# Ethernet_PHY.net
KiCad netlist of a schematic drawn in Altium Designer
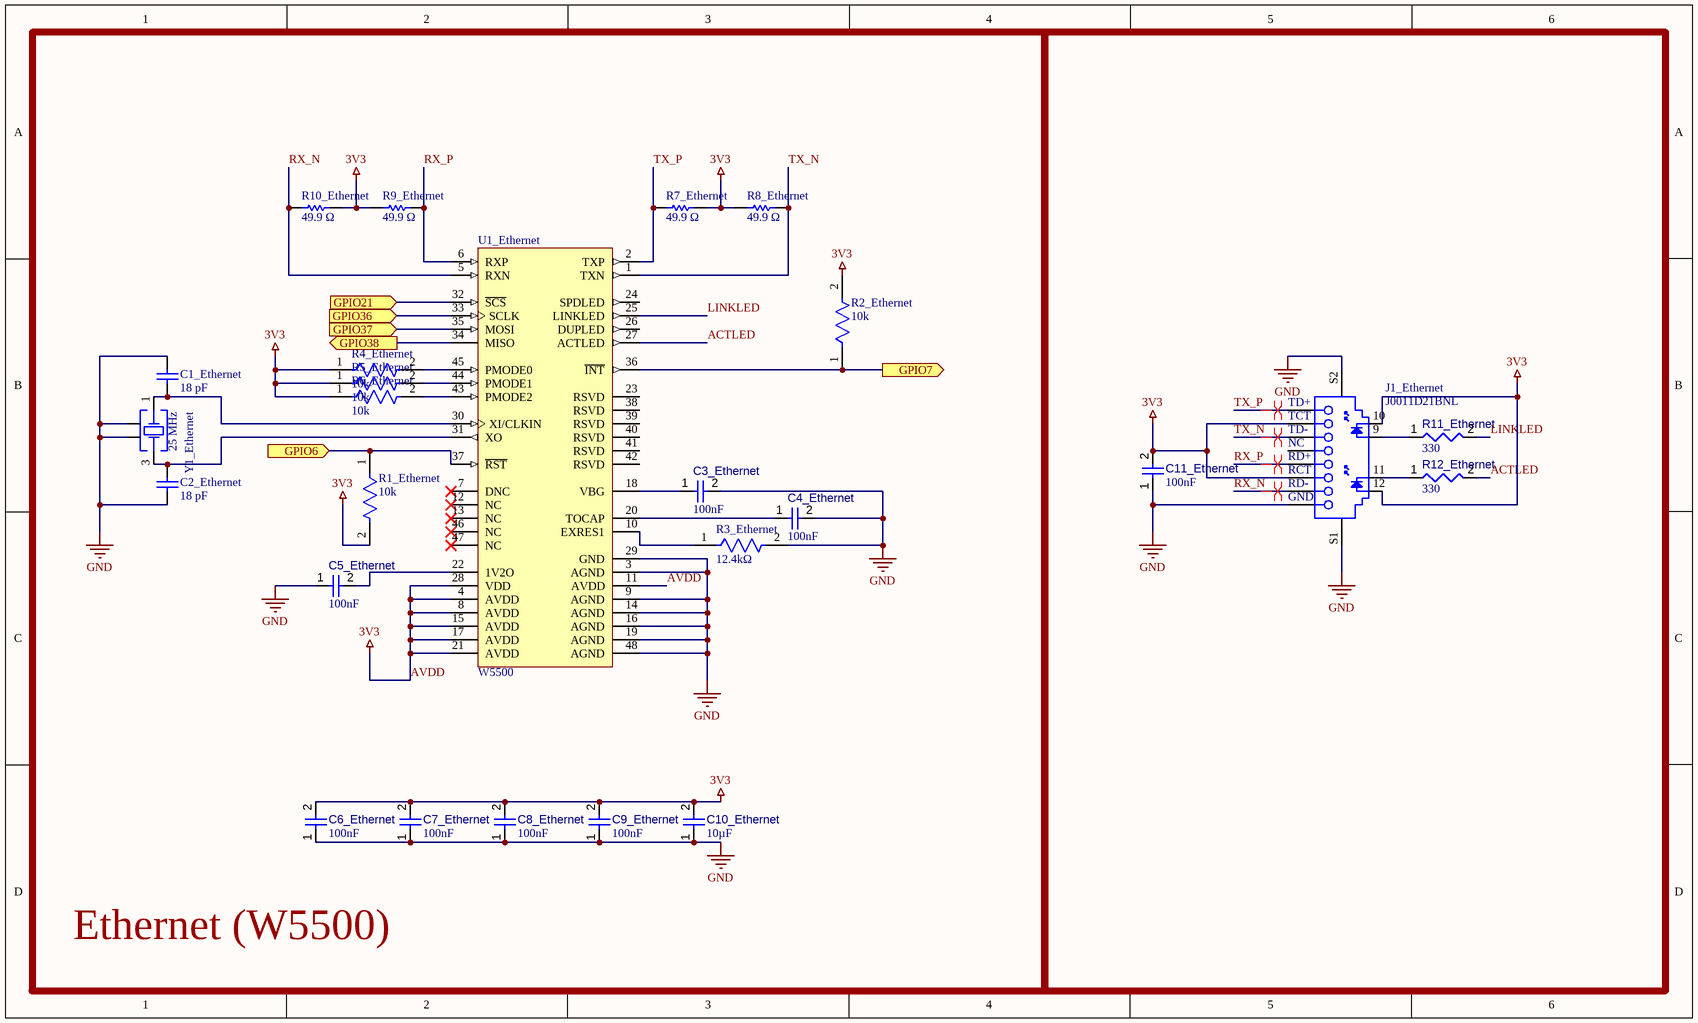
[diagram p0: Ethernet PHY.SchDoc]

(export (version "E")
  (design (tool "Eeschema 10.0.6"))
  (components
    (comp (ref "C1_Ethernet")
      (value "18 pF")
      (footprint "CAPC1608X90X35LL10T15")
      (description "Chip Capacitor, 18 pF, +/- 5%, 50 V, -55 to 125 degC, 0603 (1608 Metric), RoHS, Tape and Reel")
      (fields (field (name "TOLERANCE") "±5%") (field (name "MANUFACTURER") "Murata"))
      (libsource (lib "Altium Content Vault") (part "CAP-NP-2"))
    )
    (comp (ref "C2_Ethernet")
      (value "18 pF")
      (footprint "CAPC1608X90X35LL10T15")
      (description "Chip Capacitor, 18 pF, +/- 5%, 50 V, -55 to 125 degC, 0603 (1608 Metric), RoHS, Tape and Reel")
      (fields (field (name "TOLERANCE") "±5%") (field (name "MANUFACTURER") "Murata"))
      (libsource (lib "Altium Content Vault") (part "CAP-NP-2"))
    )
    (comp (ref "C3_Ethernet")
      (value "100nF")
      (footprint "CAPC0402(1005)60_L")
      (description "Chip Capacitor, 100nF +/-20%, 10V, 0402, Thickness 0.6 mm")
      (fields (field (name "TOLERANCE") "20%") (field (name "Comment") "Capacitor 100nF +/-20% 10V 0402"))
      (libsource (lib "Faiz Agunda") (part "CAP-NP-2"))
    )
    (comp (ref "C4_Ethernet")
      (value "100nF")
      (footprint "CAPC0402(1005)60_L")
      (description "Chip Capacitor, 100nF +/-20%, 10V, 0402, Thickness 0.6 mm")
      (fields (field (name "TOLERANCE") "20%") (field (name "Comment") "Capacitor 100nF +/-20% 10V 0402"))
      (libsource (lib "Faiz Agunda") (part "CAP-NP-2"))
    )
    (comp (ref "C5_Ethernet")
      (value "100nF")
      (footprint "CAPC0402(1005)60_L")
      (description "Chip Capacitor, 100nF +/-20%, 10V, 0402, Thickness 0.6 mm")
      (fields (field (name "TOLERANCE") "20%") (field (name "Comment") "Capacitor 100nF +/-20% 10V 0402"))
      (libsource (lib "Faiz Agunda") (part "CAP-NP-2"))
    )
    (comp (ref "C6_Ethernet")
      (value "100nF")
      (footprint "CAPC0402(1005)60_L")
      (description "Chip Capacitor, 100nF +/-20%, 10V, 0402, Thickness 0.6 mm")
      (fields (field (name "TOLERANCE") "20%") (field (name "Comment") "Capacitor 100nF +/-20% 10V 0402"))
      (libsource (lib "Faiz Agunda") (part "CAP-NP-2"))
    )
    (comp (ref "C7_Ethernet")
      (value "100nF")
      (footprint "CAPC0402(1005)60_L")
      (description "Chip Capacitor, 100nF +/-20%, 10V, 0402, Thickness 0.6 mm")
      (fields (field (name "TOLERANCE") "20%") (field (name "Comment") "Capacitor 100nF +/-20% 10V 0402"))
      (libsource (lib "Faiz Agunda") (part "CAP-NP-2"))
    )
    (comp (ref "C8_Ethernet")
      (value "100nF")
      (footprint "CAPC0402(1005)60_L")
      (description "Chip Capacitor, 100nF +/-20%, 10V, 0402, Thickness 0.6 mm")
      (fields (field (name "TOLERANCE") "20%") (field (name "Comment") "Capacitor 100nF +/-20% 10V 0402"))
      (libsource (lib "Faiz Agunda") (part "CAP-NP-2"))
    )
    (comp (ref "C9_Ethernet")
      (value "100nF")
      (footprint "CAPC0402(1005)60_L")
      (description "Chip Capacitor, 100nF +/-20%, 10V, 0402, Thickness 0.6 mm")
      (fields (field (name "TOLERANCE") "20%") (field (name "Comment") "Capacitor 100nF +/-20% 10V 0402"))
      (libsource (lib "Faiz Agunda") (part "CAP-NP-2"))
    )
    (comp (ref "C10_Ethernet")
      (value "10µF")
      (footprint "CAPC0603(1608)100_L")
      (description "Chip Capacitor, 10µF +/-20%, 10V, 0603, Thickness 1 mm")
      (fields (field (name "TOLERANCE") "10%") (field (name "Comment") "Capacitor 10µF +/-20% 10V 0603"))
      (libsource (lib "Faiz Agunda") (part "CAP-NP-2"))
    )
    (comp (ref "C11_Ethernet")
      (value "100nF")
      (footprint "CAPC0402(1005)60_L")
      (description "Chip Capacitor, 100nF +/-20%, 10V, 0402, Thickness 0.6 mm")
      (fields (field (name "TOLERANCE") "20%") (field (name "Comment") "Capacitor 100nF +/-20% 10V 0402"))
      (libsource (lib "Faiz Agunda") (part "CAP-NP-2"))
    )
    (comp (ref "J1_Ethernet")
      (value "J0011D21BNL")
      (footprint "PULS-J00XXD21XNL-B-12")
      (fields (field (name "MANUFACTURER") "Pulse"))
      (libsource (lib "Altium Content Vault") (part "PULS-RJ45-12-2SHLD"))
    )
    (comp (ref "R1_Ethernet")
      (value "10k")
      (footprint "FP-CRGCQ1206-IPC_C")
      (description "Res Thick Film 1206 10K Ohm 1% 0.25W(1/4W) ±100ppm/C Pad SMD Automotive T/R")
      (fields (field (name "TOLERANCE") "1%") (field (name "Comment") "CRGCQ1206F10K"))
      (libsource (lib "Faiz Agunda") (part "1029c3af85768c4190bb7ad29bc67b5"))
    )
    (comp (ref "R2_Ethernet")
      (value "10k")
      (footprint "FP-CRGCQ1206-IPC_C")
      (description "Res Thick Film 1206 10K Ohm 1% 0.25W(1/4W) ±100ppm/C Pad SMD Automotive T/R")
      (fields (field (name "TOLERANCE") "1%") (field (name "Comment") "CRGCQ1206F10K"))
      (libsource (lib "Faiz Agunda") (part "1029c3af85768c4190bb7ad29bc67b5"))
    )
    (comp (ref "R3_Ethernet")
      (value "12.4kΩ")
      (footprint "FP-TFCR0805-IPC_C")
      (description "RES Thin Film,  12.4kΩ, 0.1%, 0.1W, 25ppm/°C, 0805")
      (libsource (lib "Altium Content Vault") (part "1029c3af85768c4190bb7ad29bc67b5"))
    )
    (comp (ref "R4_Ethernet")
      (value "10k")
      (footprint "FP-CRGCQ1206-IPC_C")
      (description "Res Thick Film 1206 10K Ohm 1% 0.25W(1/4W) ±100ppm/C Pad SMD Automotive T/R")
      (fields (field (name "TOLERANCE") "1%") (field (name "Comment") "CRGCQ1206F10K"))
      (libsource (lib "Faiz Agunda") (part "1029c3af85768c4190bb7ad29bc67b5"))
    )
    (comp (ref "R5_Ethernet")
      (value "10k")
      (footprint "FP-CRGCQ1206-IPC_C")
      (description "Res Thick Film 1206 10K Ohm 1% 0.25W(1/4W) ±100ppm/C Pad SMD Automotive T/R")
      (fields (field (name "TOLERANCE") "1%") (field (name "Comment") "CRGCQ1206F10K"))
      (libsource (lib "Faiz Agunda") (part "1029c3af85768c4190bb7ad29bc67b5"))
    )
    (comp (ref "R6_Ethernet")
      (value "10k")
      (footprint "FP-CRGCQ1206-IPC_C")
      (description "Res Thick Film 1206 10K Ohm 1% 0.25W(1/4W) ±100ppm/C Pad SMD Automotive T/R")
      (fields (field (name "TOLERANCE") "1%") (field (name "Comment") "CRGCQ1206F10K"))
      (libsource (lib "Faiz Agunda") (part "1029c3af85768c4190bb7ad29bc67b5"))
    )
    (comp (ref "R7_Ethernet")
      (value "49.9 Ω")
      (footprint "RESC1608X55X25NL10T15")
      (libsource (lib "Altium Content Vault") (part "RES-2"))
    )
    (comp (ref "R8_Ethernet")
      (value "49.9 Ω")
      (footprint "RESC1608X55X25NL10T15")
      (libsource (lib "Altium Content Vault") (part "RES-2"))
    )
    (comp (ref "R9_Ethernet")
      (value "49.9 Ω")
      (footprint "RESC1608X55X25NL10T15")
      (libsource (lib "Altium Content Vault") (part "RES-2"))
    )
    (comp (ref "R10_Ethernet")
      (value "49.9 Ω")
      (footprint "RESC1608X55X25NL10T15")
      (libsource (lib "Altium Content Vault") (part "RES-2"))
    )
    (comp (ref "R11_Ethernet")
      (value "330")
      (footprint "RESC0402(1005)_L")
      (description "Chip Resistor, 330 Ohms, +/-5 %, 63 mW, -55 to 155 degC, 0402")
      (fields (field (name "POWER") "63mW") (field (name "TOLERANCE") "5%"))
      (libsource (lib "Faiz Agunda") (part "RES-2"))
    )
    (comp (ref "R12_Ethernet")
      (value "330")
      (footprint "RESC0402(1005)_L")
      (description "Chip Resistor, 330 Ohms, +/-5 %, 63 mW, -55 to 155 degC, 0402")
      (fields (field (name "POWER") "63mW") (field (name "TOLERANCE") "5%"))
      (libsource (lib "Faiz Agunda") (part "RES-2"))
    )
    (comp (ref "U1_Ethernet")
      (value "W5500")
      (footprint "WIZ-W5500-LQFP-48_M")
      (fields (field (name "MANUFACTURER") "WIZnet"))
      (libsource (lib "Faiz Agunda") (part "WIZ-W5500-LQFP-48"))
    )
    (comp (ref "Y1_Ethernet")
      (value "25 MHz")
      (footprint "WE-XTAL_CFPX-180")
      (description "WE-XTAL Quartz Crystal")
      (libsource (lib "Altium Content Vault") (part "WE-XTAL_CFPX-180"))
    )
  )
  (nets
    (net (code "1") (name "/ACTLED") (class "Default")
      (node (ref "R12_Ethernet") (pin "2") (pinfunction "2_2") (pintype "passive"))
      (node (ref "U1_Ethernet") (pin "27") (pinfunction "ACTLED_27") (pintype "output"))
    )
    (net (code "2") (name "/GPIO6") (class "Default")
      (node (ref "R1_Ethernet") (pin "1") (pinfunction "1_1") (pintype "passive"))
      (node (ref "U1_Ethernet") (pin "37") (pinfunction "~{RST}_37") (pintype "input"))
    )
    (net (code "3") (name "/GPIO7") (class "Default")
      (node (ref "R2_Ethernet") (pin "1") (pinfunction "1_1") (pintype "passive"))
      (node (ref "U1_Ethernet") (pin "36") (pinfunction "~{INT}_36") (pintype "output"))
    )
    (net (code "4") (name "/GPIO21") (class "Default")
      (node (ref "U1_Ethernet") (pin "32") (pinfunction "~{SCS}_32") (pintype "input"))
    )
    (net (code "5") (name "/GPIO36") (class "Default")
      (node (ref "U1_Ethernet") (pin "33") (pinfunction "SCLK_33") (pintype "input"))
    )
    (net (code "6") (name "/GPIO37") (class "Default")
      (node (ref "U1_Ethernet") (pin "35") (pinfunction "MOSI_35") (pintype "input"))
    )
    (net (code "7") (name "/GPIO38") (class "Default")
      (node (ref "U1_Ethernet") (pin "34") (pinfunction "MISO_34") (pintype "tri_state"))
    )
    (net (code "8") (name "/LINKLED") (class "Default")
      (node (ref "R11_Ethernet") (pin "2") (pinfunction "2_2") (pintype "passive"))
      (node (ref "U1_Ethernet") (pin "25") (pinfunction "LINKLED_25") (pintype "output"))
    )
    (net (code "9") (name "/RX_N") (class "Default")
      (node (ref "J1_Ethernet") (pin "6") (pinfunction "RD-_6") (pintype "passive"))
      (node (ref "R10_Ethernet") (pin "1") (pinfunction "1_1") (pintype "passive"))
      (node (ref "U1_Ethernet") (pin "5") (pinfunction "RXN_5") (pintype "input"))
    )
    (net (code "10") (name "/RX_P") (class "Default")
      (node (ref "J1_Ethernet") (pin "3") (pinfunction "RD+_3") (pintype "passive"))
      (node (ref "R9_Ethernet") (pin "2") (pinfunction "2_2") (pintype "passive"))
      (node (ref "U1_Ethernet") (pin "6") (pinfunction "RXP_6") (pintype "input"))
    )
    (net (code "11") (name "/TX_N") (class "Default")
      (node (ref "J1_Ethernet") (pin "2") (pinfunction "TD-_2") (pintype "passive"))
      (node (ref "R8_Ethernet") (pin "2") (pinfunction "2_2") (pintype "passive"))
      (node (ref "U1_Ethernet") (pin "1") (pinfunction "TXN_1") (pintype "output"))
    )
    (net (code "12") (name "/TX_P") (class "Default")
      (node (ref "J1_Ethernet") (pin "1") (pinfunction "TD+_1") (pintype "passive"))
      (node (ref "R7_Ethernet") (pin "1") (pinfunction "1_1") (pintype "passive"))
      (node (ref "U1_Ethernet") (pin "2") (pinfunction "TXP_2") (pintype "output"))
    )
    (net (code "13") (name "3V3") (class "Default")
      (node (ref "C10_Ethernet") (pin "2") (pinfunction "2_2") (pintype "passive"))
      (node (ref "C11_Ethernet") (pin "2") (pinfunction "2_2") (pintype "passive"))
      (node (ref "C6_Ethernet") (pin "2") (pinfunction "2_2") (pintype "passive"))
      (node (ref "C7_Ethernet") (pin "2") (pinfunction "2_2") (pintype "passive"))
      (node (ref "C8_Ethernet") (pin "2") (pinfunction "2_2") (pintype "passive"))
      (node (ref "C9_Ethernet") (pin "2") (pinfunction "2_2") (pintype "passive"))
      (node (ref "J1_Ethernet") (pin "10") (pinfunction "10_10") (pintype "passive"))
      (node (ref "J1_Ethernet") (pin "12") (pinfunction "12_12") (pintype "passive"))
      (node (ref "J1_Ethernet") (pin "4") (pinfunction "TCT_4") (pintype "passive"))
      (node (ref "J1_Ethernet") (pin "5") (pinfunction "RCT_5") (pintype "passive"))
      (node (ref "R10_Ethernet") (pin "2") (pinfunction "2_2") (pintype "passive"))
      (node (ref "R1_Ethernet") (pin "2") (pinfunction "2_2") (pintype "passive"))
      (node (ref "R2_Ethernet") (pin "2") (pinfunction "2_2") (pintype "passive"))
      (node (ref "R4_Ethernet") (pin "1") (pinfunction "1_1") (pintype "passive"))
      (node (ref "R5_Ethernet") (pin "1") (pinfunction "1_1") (pintype "passive"))
      (node (ref "R6_Ethernet") (pin "1") (pinfunction "1_1") (pintype "passive"))
      (node (ref "R7_Ethernet") (pin "2") (pinfunction "2_2") (pintype "passive"))
      (node (ref "R8_Ethernet") (pin "1") (pinfunction "1_1") (pintype "passive"))
      (node (ref "R9_Ethernet") (pin "1") (pinfunction "1_1") (pintype "passive"))
      (node (ref "U1_Ethernet") (pin "11") (pinfunction "AVDD_11") (pintype "power_in"))
      (node (ref "U1_Ethernet") (pin "15") (pinfunction "AVDD_15") (pintype "power_in"))
      (node (ref "U1_Ethernet") (pin "17") (pinfunction "AVDD_17") (pintype "power_in"))
      (node (ref "U1_Ethernet") (pin "21") (pinfunction "AVDD_21") (pintype "power_in"))
      (node (ref "U1_Ethernet") (pin "28") (pinfunction "VDD_28") (pintype "power_in"))
      (node (ref "U1_Ethernet") (pin "4") (pinfunction "AVDD_4") (pintype "power_in"))
      (node (ref "U1_Ethernet") (pin "8") (pinfunction "AVDD_8") (pintype "power_in"))
    )
    (net (code "14") (name "GND") (class "Default")
      (node (ref "C10_Ethernet") (pin "1") (pinfunction "1_1") (pintype "passive"))
      (node (ref "C11_Ethernet") (pin "1") (pinfunction "1_1") (pintype "passive"))
      (node (ref "C1_Ethernet") (pin "2") (pinfunction "2_2") (pintype "passive"))
      (node (ref "C2_Ethernet") (pin "1") (pinfunction "1_1") (pintype "passive"))
      (node (ref "C3_Ethernet") (pin "2") (pinfunction "2_2") (pintype "passive"))
      (node (ref "C4_Ethernet") (pin "2") (pinfunction "2_2") (pintype "passive"))
      (node (ref "C5_Ethernet") (pin "1") (pinfunction "1_1") (pintype "passive"))
      (node (ref "C6_Ethernet") (pin "1") (pinfunction "1_1") (pintype "passive"))
      (node (ref "C7_Ethernet") (pin "1") (pinfunction "1_1") (pintype "passive"))
      (node (ref "C8_Ethernet") (pin "1") (pinfunction "1_1") (pintype "passive"))
      (node (ref "C9_Ethernet") (pin "1") (pinfunction "1_1") (pintype "passive"))
      (node (ref "J1_Ethernet") (pin "8") (pinfunction "CHS_GROUND_8") (pintype "passive"))
      (node (ref "J1_Ethernet") (pin "S1") (pinfunction "S1_S1") (pintype "passive"))
      (node (ref "J1_Ethernet") (pin "S2") (pinfunction "S2_S2") (pintype "passive"))
      (node (ref "R3_Ethernet") (pin "2") (pinfunction "2_2") (pintype "passive"))
      (node (ref "U1_Ethernet") (pin "14") (pinfunction "AGND_14") (pintype "power_in"))
      (node (ref "U1_Ethernet") (pin "16") (pinfunction "AGND_16") (pintype "power_in"))
      (node (ref "U1_Ethernet") (pin "19") (pinfunction "AGND_19") (pintype "power_in"))
      (node (ref "U1_Ethernet") (pin "29") (pinfunction "GND_29") (pintype "power_in"))
      (node (ref "U1_Ethernet") (pin "3") (pinfunction "AGND_3") (pintype "power_in"))
      (node (ref "U1_Ethernet") (pin "48") (pinfunction "AGND_48") (pintype "power_in"))
      (node (ref "U1_Ethernet") (pin "9") (pinfunction "AGND_9") (pintype "power_in"))
      (node (ref "Y1_Ethernet") (pin "2") (pinfunction "GND&Lid_2") (pintype "passive"))
      (node (ref "Y1_Ethernet") (pin "4") (pinfunction "GND&Lid_4") (pintype "passive"))
    )
    (net (code "15") (name "Net-(J1_Ethernet-Pad9)") (class "Default")
      (node (ref "J1_Ethernet") (pin "9") (pinfunction "9_9") (pintype "passive"))
      (node (ref "R11_Ethernet") (pin "1") (pinfunction "1_1") (pintype "passive"))
    )
    (net (code "16") (name "Net-(J1_Ethernet-Pad11)") (class "Default")
      (node (ref "J1_Ethernet") (pin "11") (pinfunction "11_11") (pintype "passive"))
      (node (ref "R12_Ethernet") (pin "1") (pinfunction "1_1") (pintype "passive"))
    )
    (net (code "17") (name "Net-(U1_Ethernet-1V2O)") (class "Default")
      (node (ref "C5_Ethernet") (pin "2") (pinfunction "2_2") (pintype "passive"))
      (node (ref "U1_Ethernet") (pin "22") (pinfunction "1V2O_22") (pintype "power_in"))
    )
    (net (code "18") (name "Net-(U1_Ethernet-EXRES1)") (class "Default")
      (node (ref "R3_Ethernet") (pin "1") (pinfunction "1_1") (pintype "passive"))
      (node (ref "U1_Ethernet") (pin "10") (pinfunction "EXRES1_10") (pintype "passive"))
    )
    (net (code "19") (name "Net-(U1_Ethernet-PMODE0)") (class "Default")
      (node (ref "R4_Ethernet") (pin "2") (pinfunction "2_2") (pintype "passive"))
      (node (ref "U1_Ethernet") (pin "45") (pinfunction "PMODE0_45") (pintype "input"))
    )
    (net (code "20") (name "Net-(U1_Ethernet-PMODE1)") (class "Default")
      (node (ref "R5_Ethernet") (pin "2") (pinfunction "2_2") (pintype "passive"))
      (node (ref "U1_Ethernet") (pin "44") (pinfunction "PMODE1_44") (pintype "input"))
    )
    (net (code "21") (name "Net-(U1_Ethernet-PMODE2)") (class "Default")
      (node (ref "R6_Ethernet") (pin "2") (pinfunction "2_2") (pintype "passive"))
      (node (ref "U1_Ethernet") (pin "43") (pinfunction "PMODE2_43") (pintype "input"))
    )
    (net (code "22") (name "Net-(U1_Ethernet-TOCAP)") (class "Default")
      (node (ref "C4_Ethernet") (pin "1") (pinfunction "1_1") (pintype "passive"))
      (node (ref "U1_Ethernet") (pin "20") (pinfunction "TOCAP_20") (pintype "passive"))
    )
    (net (code "23") (name "Net-(U1_Ethernet-VBG)") (class "Default")
      (node (ref "C3_Ethernet") (pin "1") (pinfunction "1_1") (pintype "passive"))
      (node (ref "U1_Ethernet") (pin "18") (pinfunction "VBG_18") (pintype "passive"))
    )
    (net (code "24") (name "Net-(U1_Ethernet-XI{slash}CLKIN)") (class "Default")
      (node (ref "C1_Ethernet") (pin "1") (pinfunction "1_1") (pintype "passive"))
      (node (ref "U1_Ethernet") (pin "30") (pinfunction "XI/CLKIN_30") (pintype "input"))
      (node (ref "Y1_Ethernet") (pin "1") (pinfunction "Crystal_1") (pintype "passive"))
    )
    (net (code "25") (name "Net-(U1_Ethernet-XO)") (class "Default")
      (node (ref "C2_Ethernet") (pin "2") (pinfunction "2_2") (pintype "passive"))
      (node (ref "U1_Ethernet") (pin "31") (pinfunction "XO_31") (pintype "output"))
      (node (ref "Y1_Ethernet") (pin "3") (pinfunction "Crystal_3") (pintype "passive"))
    )
    (net (code "26") (name "unconnected-(J1_Ethernet-NC-Pad7)") (class "Default")
      (node (ref "J1_Ethernet") (pin "7") (pinfunction "NC_7") (pintype "passive"))
    )
    (net (code "27") (name "unconnected-(U1_Ethernet-DNC-Pad7)") (class "Default")
      (node (ref "U1_Ethernet") (pin "7") (pinfunction "DNC_7") (pintype "passive+no_connect"))
    )
    (net (code "28") (name "unconnected-(U1_Ethernet-DUPLED-Pad26)") (class "Default")
      (node (ref "U1_Ethernet") (pin "26") (pinfunction "DUPLED_26") (pintype "output"))
    )
    (net (code "29") (name "unconnected-(U1_Ethernet-NC-Pad12)") (class "Default")
      (node (ref "U1_Ethernet") (pin "12") (pinfunction "NC_12") (pintype "passive+no_connect"))
    )
    (net (code "30") (name "unconnected-(U1_Ethernet-NC-Pad13)") (class "Default")
      (node (ref "U1_Ethernet") (pin "13") (pinfunction "NC_13") (pintype "passive+no_connect"))
    )
    (net (code "31") (name "unconnected-(U1_Ethernet-NC-Pad46)") (class "Default")
      (node (ref "U1_Ethernet") (pin "46") (pinfunction "NC_46") (pintype "passive+no_connect"))
    )
    (net (code "32") (name "unconnected-(U1_Ethernet-NC-Pad47)") (class "Default")
      (node (ref "U1_Ethernet") (pin "47") (pinfunction "NC_47") (pintype "passive+no_connect"))
    )
    (net (code "33") (name "unconnected-(U1_Ethernet-RSVD-Pad23)") (class "Default")
      (node (ref "U1_Ethernet") (pin "23") (pinfunction "RSVD_23") (pintype "passive"))
    )
    (net (code "34") (name "unconnected-(U1_Ethernet-RSVD-Pad38)") (class "Default")
      (node (ref "U1_Ethernet") (pin "38") (pinfunction "RSVD_38") (pintype "passive"))
    )
    (net (code "35") (name "unconnected-(U1_Ethernet-RSVD-Pad39)") (class "Default")
      (node (ref "U1_Ethernet") (pin "39") (pinfunction "RSVD_39") (pintype "passive"))
    )
    (net (code "36") (name "unconnected-(U1_Ethernet-RSVD-Pad40)") (class "Default")
      (node (ref "U1_Ethernet") (pin "40") (pinfunction "RSVD_40") (pintype "passive"))
    )
    (net (code "37") (name "unconnected-(U1_Ethernet-RSVD-Pad41)") (class "Default")
      (node (ref "U1_Ethernet") (pin "41") (pinfunction "RSVD_41") (pintype "passive"))
    )
    (net (code "38") (name "unconnected-(U1_Ethernet-RSVD-Pad42)") (class "Default")
      (node (ref "U1_Ethernet") (pin "42") (pinfunction "RSVD_42") (pintype "passive"))
    )
    (net (code "39") (name "unconnected-(U1_Ethernet-SPDLED-Pad24)") (class "Default")
      (node (ref "U1_Ethernet") (pin "24") (pinfunction "SPDLED_24") (pintype "output"))
    )
  )
)
